# Sheet.net
KiCad netlist of a schematic drawn in Altium Designer
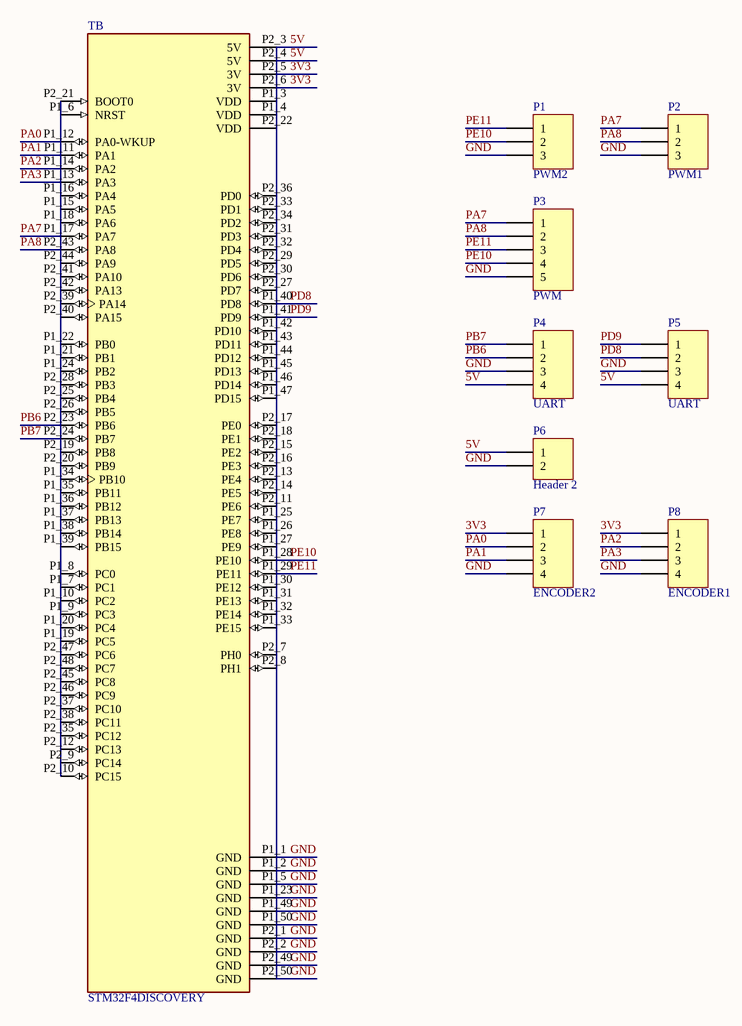
[diagram p0: Sheet.SchDoc]

(export (version "E")
  (design (tool "Eeschema 10.0.6"))
  (components
    (comp (ref "P1")
      (value "PWM2")
      (footprint "HDR1X3")
      (description "Header, 3-Pin")
      (fields (field (name "PUBLISHER") "Altium Limited"))
      (libsource (lib "Miscellaneous Connectors") (part "Header 3"))
    )
    (comp (ref "P2")
      (value "PWM1")
      (footprint "HDR1X3")
      (description "Header, 3-Pin")
      (fields (field (name "PUBLISHER") "Altium Limited"))
      (libsource (lib "Miscellaneous Connectors") (part "Header 3"))
    )
    (comp (ref "P3")
      (value "PWM")
      (footprint "HDR1X5")
      (description "Header, 5-Pin")
      (fields (field (name "PUBLISHER") "Altium Limited"))
      (libsource (lib "Miscellaneous Connectors") (part "Header 5"))
    )
    (comp (ref "P4")
      (value "UART")
      (footprint "HDR1X4")
      (description "Header, 4-Pin")
      (fields (field (name "PUBLISHER") "Altium Limited"))
      (libsource (lib "Miscellaneous Connectors") (part "Header 4"))
    )
    (comp (ref "P5")
      (value "UART")
      (footprint "HDR1X4")
      (description "Header, 4-Pin")
      (fields (field (name "PUBLISHER") "Altium Limited"))
      (libsource (lib "Miscellaneous Connectors") (part "Header 4"))
    )
    (comp (ref "P6")
      (value "Header 2")
      (footprint "HDR1X2")
      (description "Header, 2-Pin")
      (fields (field (name "PUBLISHER") "Altium Limited"))
      (libsource (lib "Miscellaneous Connectors") (part "Header 2"))
    )
    (comp (ref "P7")
      (value "ENCODER2")
      (footprint "HDR1X4")
      (description "Header, 4-Pin")
      (fields (field (name "PUBLISHER") "Altium Limited"))
      (libsource (lib "Miscellaneous Connectors") (part "Header 4"))
    )
    (comp (ref "P8")
      (value "ENCODER1")
      (footprint "HDR1X4")
      (description "Header, 4-Pin")
      (fields (field (name "PUBLISHER") "Altium Limited"))
      (libsource (lib "Miscellaneous Connectors") (part "Header 4"))
    )
    (comp (ref "TB")
      (value "STM32F4DISCOVERY")
      (footprint "MODULE_STM32F4DISCOVERY")
      (description "STM32F407VGT6 Discovery STM32F4 ARMÂ® CortexÂ®-M4 MCU 32-Bit Embedded Evaluation Board")
      (fields (field (name "MF") "STMicroelectronics"))
      (libsource (lib "STM32F4DISCOVERY") (part "STM32F4DISCOVERY"))
    )
  )
  (nets
    (net (code "1") (name "/3V3") (class "Default")
      (node (ref "P1") (pin "1") (pinfunction "1_1") (pintype "passive"))
      (node (ref "P1") (pin "2") (pinfunction "2_2") (pintype "passive"))
      (node (ref "P1") (pin "3") (pinfunction "3_3") (pintype "passive"))
      (node (ref "P2") (pin "3") (pinfunction "3_3") (pintype "passive"))
      (node (ref "P3") (pin "3") (pinfunction "3_3") (pintype "passive"))
      (node (ref "P3") (pin "4") (pinfunction "4_4") (pintype "passive"))
      (node (ref "P3") (pin "5") (pinfunction "5_5") (pintype "passive"))
      (node (ref "P4") (pin "3") (pinfunction "3_3") (pintype "passive"))
      (node (ref "P4") (pin "4") (pinfunction "4_4") (pintype "passive"))
      (node (ref "P5") (pin "1") (pinfunction "1_1") (pintype "passive"))
      (node (ref "P5") (pin "2") (pinfunction "2_2") (pintype "passive"))
      (node (ref "P5") (pin "3") (pinfunction "3_3") (pintype "passive"))
      (node (ref "P5") (pin "4") (pinfunction "4_4") (pintype "passive"))
      (node (ref "P6") (pin "1") (pinfunction "1_1") (pintype "passive"))
      (node (ref "P6") (pin "2") (pinfunction "2_2") (pintype "passive"))
      (node (ref "P7") (pin "1") (pinfunction "1_1") (pintype "passive"))
      (node (ref "P7") (pin "4") (pinfunction "4_4") (pintype "passive"))
      (node (ref "P8") (pin "1") (pinfunction "1_1") (pintype "passive"))
      (node (ref "P8") (pin "4") (pinfunction "4_4") (pintype "passive"))
      (node (ref "TB") (pin "P1_1") (pinfunction "GND_P1_1") (pintype "power_in"))
      (node (ref "TB") (pin "P1_2") (pinfunction "GND_P1_2") (pintype "power_in"))
      (node (ref "TB") (pin "P1_23") (pinfunction "GND_P1_23") (pintype "power_in"))
      (node (ref "TB") (pin "P1_25") (pinfunction "PE7_P1_25") (pintype "bidirectional"))
      (node (ref "TB") (pin "P1_26") (pinfunction "PE8_P1_26") (pintype "bidirectional"))
      (node (ref "TB") (pin "P1_27") (pinfunction "PE9_P1_27") (pintype "bidirectional"))
      (node (ref "TB") (pin "P1_28") (pinfunction "PE10_P1_28") (pintype "bidirectional"))
      (node (ref "TB") (pin "P1_29") (pinfunction "PE11_P1_29") (pintype "bidirectional"))
      (node (ref "TB") (pin "P1_3") (pinfunction "VDD_P1_3") (pintype "power_in"))
      (node (ref "TB") (pin "P1_30") (pinfunction "PE12_P1_30") (pintype "bidirectional"))
      (node (ref "TB") (pin "P1_31") (pinfunction "PE13_P1_31") (pintype "bidirectional"))
      (node (ref "TB") (pin "P1_32") (pinfunction "PE14_P1_32") (pintype "bidirectional"))
      (node (ref "TB") (pin "P1_33") (pinfunction "PE15_P1_33") (pintype "bidirectional"))
      (node (ref "TB") (pin "P1_4") (pinfunction "VDD_P1_4") (pintype "power_in"))
      (node (ref "TB") (pin "P1_40") (pinfunction "PD8_P1_40") (pintype "bidirectional"))
      (node (ref "TB") (pin "P1_41") (pinfunction "PD9_P1_41") (pintype "bidirectional"))
      (node (ref "TB") (pin "P1_42") (pinfunction "PD10_P1_42") (pintype "bidirectional"))
      (node (ref "TB") (pin "P1_43") (pinfunction "PD11_P1_43") (pintype "bidirectional"))
      (node (ref "TB") (pin "P1_44") (pinfunction "PD12_P1_44") (pintype "bidirectional"))
      (node (ref "TB") (pin "P1_45") (pinfunction "PD13_P1_45") (pintype "bidirectional"))
      (node (ref "TB") (pin "P1_46") (pinfunction "PD14_P1_46") (pintype "bidirectional"))
      (node (ref "TB") (pin "P1_47") (pinfunction "PD15_P1_47") (pintype "bidirectional"))
      (node (ref "TB") (pin "P1_49") (pinfunction "GND_P1_49") (pintype "power_in"))
      (node (ref "TB") (pin "P1_5") (pinfunction "GND_P1_5") (pintype "power_in"))
      (node (ref "TB") (pin "P1_50") (pinfunction "GND_P1_50") (pintype "power_in"))
      (node (ref "TB") (pin "P2_1") (pinfunction "GND_P2_1") (pintype "power_in"))
      (node (ref "TB") (pin "P2_11") (pinfunction "PE6_P2_11") (pintype "bidirectional"))
      (node (ref "TB") (pin "P2_13") (pinfunction "PE4_P2_13") (pintype "bidirectional"))
      (node (ref "TB") (pin "P2_14") (pinfunction "PE5_P2_14") (pintype "bidirectional"))
      (node (ref "TB") (pin "P2_15") (pinfunction "PE2_P2_15") (pintype "bidirectional"))
      (node (ref "TB") (pin "P2_16") (pinfunction "PE3_P2_16") (pintype "bidirectional"))
      (node (ref "TB") (pin "P2_17") (pinfunction "PE0_P2_17") (pintype "bidirectional"))
      (node (ref "TB") (pin "P2_18") (pinfunction "PE1_P2_18") (pintype "bidirectional"))
      (node (ref "TB") (pin "P2_2") (pinfunction "GND_P2_2") (pintype "power_in"))
      (node (ref "TB") (pin "P2_22") (pinfunction "VDD_P2_22") (pintype "power_in"))
      (node (ref "TB") (pin "P2_27") (pinfunction "PD7_P2_27") (pintype "bidirectional"))
      (node (ref "TB") (pin "P2_29") (pinfunction "PD5_P2_29") (pintype "bidirectional"))
      (node (ref "TB") (pin "P2_3") (pinfunction "5V_P2_3") (pintype "power_in"))
      (node (ref "TB") (pin "P2_30") (pinfunction "PD6_P2_30") (pintype "bidirectional"))
      (node (ref "TB") (pin "P2_31") (pinfunction "PD3_P2_31") (pintype "bidirectional"))
      (node (ref "TB") (pin "P2_32") (pinfunction "PD4_P2_32") (pintype "bidirectional"))
      (node (ref "TB") (pin "P2_33") (pinfunction "PD1_P2_33") (pintype "bidirectional"))
      (node (ref "TB") (pin "P2_34") (pinfunction "PD2_P2_34") (pintype "bidirectional"))
      (node (ref "TB") (pin "P2_36") (pinfunction "PD0_P2_36") (pintype "bidirectional"))
      (node (ref "TB") (pin "P2_4") (pinfunction "5V_P2_4") (pintype "power_in"))
      (node (ref "TB") (pin "P2_49") (pinfunction "GND_P2_49") (pintype "power_in"))
      (node (ref "TB") (pin "P2_5") (pinfunction "3V_P2_5") (pintype "power_in"))
      (node (ref "TB") (pin "P2_50") (pinfunction "GND_P2_50") (pintype "power_in"))
      (node (ref "TB") (pin "P2_6") (pinfunction "3V_P2_6") (pintype "power_in"))
      (node (ref "TB") (pin "P2_7") (pinfunction "PH0_P2_7") (pintype "bidirectional"))
      (node (ref "TB") (pin "P2_8") (pinfunction "PH1_P2_8") (pintype "bidirectional"))
    )
    (net (code "2") (name "/PA0") (class "Default")
      (node (ref "P2") (pin "1") (pinfunction "1_1") (pintype "passive"))
      (node (ref "P2") (pin "2") (pinfunction "2_2") (pintype "passive"))
      (node (ref "P3") (pin "1") (pinfunction "1_1") (pintype "passive"))
      (node (ref "P3") (pin "2") (pinfunction "2_2") (pintype "passive"))
      (node (ref "P4") (pin "1") (pinfunction "1_1") (pintype "passive"))
      (node (ref "P4") (pin "2") (pinfunction "2_2") (pintype "passive"))
      (node (ref "P7") (pin "2") (pinfunction "2_2") (pintype "passive"))
      (node (ref "P7") (pin "3") (pinfunction "3_3") (pintype "passive"))
      (node (ref "P8") (pin "2") (pinfunction "2_2") (pintype "passive"))
      (node (ref "P8") (pin "3") (pinfunction "3_3") (pintype "passive"))
      (node (ref "TB") (pin "P1_10") (pinfunction "PC2_P1_10") (pintype "bidirectional"))
      (node (ref "TB") (pin "P1_11") (pinfunction "PA1_P1_11") (pintype "bidirectional"))
      (node (ref "TB") (pin "P1_12") (pinfunction "PA0-WKUP_P1_12") (pintype "bidirectional"))
      (node (ref "TB") (pin "P1_13") (pinfunction "PA3_P1_13") (pintype "bidirectional"))
      (node (ref "TB") (pin "P1_14") (pinfunction "PA2_P1_14") (pintype "bidirectional"))
      (node (ref "TB") (pin "P1_15") (pinfunction "PA5_P1_15") (pintype "bidirectional"))
      (node (ref "TB") (pin "P1_16") (pinfunction "PA4_P1_16") (pintype "bidirectional"))
      (node (ref "TB") (pin "P1_17") (pinfunction "PA7_P1_17") (pintype "bidirectional"))
      (node (ref "TB") (pin "P1_18") (pinfunction "PA6_P1_18") (pintype "bidirectional"))
      (node (ref "TB") (pin "P1_19") (pinfunction "PC5_P1_19") (pintype "bidirectional"))
      (node (ref "TB") (pin "P1_20") (pinfunction "PC4_P1_20") (pintype "bidirectional"))
      (node (ref "TB") (pin "P1_21") (pinfunction "PB1_P1_21") (pintype "bidirectional"))
      (node (ref "TB") (pin "P1_22") (pinfunction "PB0_P1_22") (pintype "bidirectional"))
      (node (ref "TB") (pin "P1_24") (pinfunction "PB2_P1_24") (pintype "bidirectional"))
      (node (ref "TB") (pin "P1_34") (pinfunction "PB10_P1_34") (pintype "bidirectional"))
      (node (ref "TB") (pin "P1_35") (pinfunction "PB11_P1_35") (pintype "bidirectional"))
      (node (ref "TB") (pin "P1_36") (pinfunction "PB12_P1_36") (pintype "bidirectional"))
      (node (ref "TB") (pin "P1_37") (pinfunction "PB13_P1_37") (pintype "bidirectional"))
      (node (ref "TB") (pin "P1_38") (pinfunction "PB14_P1_38") (pintype "bidirectional"))
      (node (ref "TB") (pin "P1_39") (pinfunction "PB15_P1_39") (pintype "bidirectional"))
      (node (ref "TB") (pin "P1_6") (pinfunction "NRST_P1_6") (pintype "input"))
      (node (ref "TB") (pin "P1_7") (pinfunction "PC1_P1_7") (pintype "bidirectional"))
      (node (ref "TB") (pin "P1_8") (pinfunction "PC0_P1_8") (pintype "bidirectional"))
      (node (ref "TB") (pin "P1_9") (pinfunction "PC3_P1_9") (pintype "bidirectional"))
      (node (ref "TB") (pin "P2_10") (pinfunction "PC15_P2_10") (pintype "bidirectional"))
      (node (ref "TB") (pin "P2_12") (pinfunction "PC13_P2_12") (pintype "bidirectional"))
      (node (ref "TB") (pin "P2_19") (pinfunction "PB8_P2_19") (pintype "bidirectional"))
      (node (ref "TB") (pin "P2_20") (pinfunction "PB9_P2_20") (pintype "bidirectional"))
      (node (ref "TB") (pin "P2_21") (pinfunction "BOOT0_P2_21") (pintype "input"))
      (node (ref "TB") (pin "P2_23") (pinfunction "PB6_P2_23") (pintype "bidirectional"))
      (node (ref "TB") (pin "P2_24") (pinfunction "PB7_P2_24") (pintype "bidirectional"))
      (node (ref "TB") (pin "P2_25") (pinfunction "PB4_P2_25") (pintype "bidirectional"))
      (node (ref "TB") (pin "P2_26") (pinfunction "PB5_P2_26") (pintype "bidirectional"))
      (node (ref "TB") (pin "P2_28") (pinfunction "PB3_P2_28") (pintype "bidirectional"))
      (node (ref "TB") (pin "P2_35") (pinfunction "PC12_P2_35") (pintype "bidirectional"))
      (node (ref "TB") (pin "P2_37") (pinfunction "PC10_P2_37") (pintype "bidirectional"))
      (node (ref "TB") (pin "P2_38") (pinfunction "PC11_P2_38") (pintype "bidirectional"))
      (node (ref "TB") (pin "P2_39") (pinfunction "PA14_P2_39") (pintype "bidirectional"))
      (node (ref "TB") (pin "P2_40") (pinfunction "PA15_P2_40") (pintype "bidirectional"))
      (node (ref "TB") (pin "P2_41") (pinfunction "PA10_P2_41") (pintype "bidirectional"))
      (node (ref "TB") (pin "P2_42") (pinfunction "PA13_P2_42") (pintype "bidirectional"))
      (node (ref "TB") (pin "P2_43") (pinfunction "PA8_P2_43") (pintype "bidirectional"))
      (node (ref "TB") (pin "P2_44") (pinfunction "PA9_P2_44") (pintype "bidirectional"))
      (node (ref "TB") (pin "P2_45") (pinfunction "PC8_P2_45") (pintype "bidirectional"))
      (node (ref "TB") (pin "P2_46") (pinfunction "PC9_P2_46") (pintype "bidirectional"))
      (node (ref "TB") (pin "P2_47") (pinfunction "PC6_P2_47") (pintype "bidirectional"))
      (node (ref "TB") (pin "P2_48") (pinfunction "PC7_P2_48") (pintype "bidirectional"))
      (node (ref "TB") (pin "P2_9") (pinfunction "PC14_P2_9") (pintype "bidirectional"))
    )
  )
)
